# ARC_Lighting_v1_0.net
KiCad netlist of a schematic drawn in EAGLE
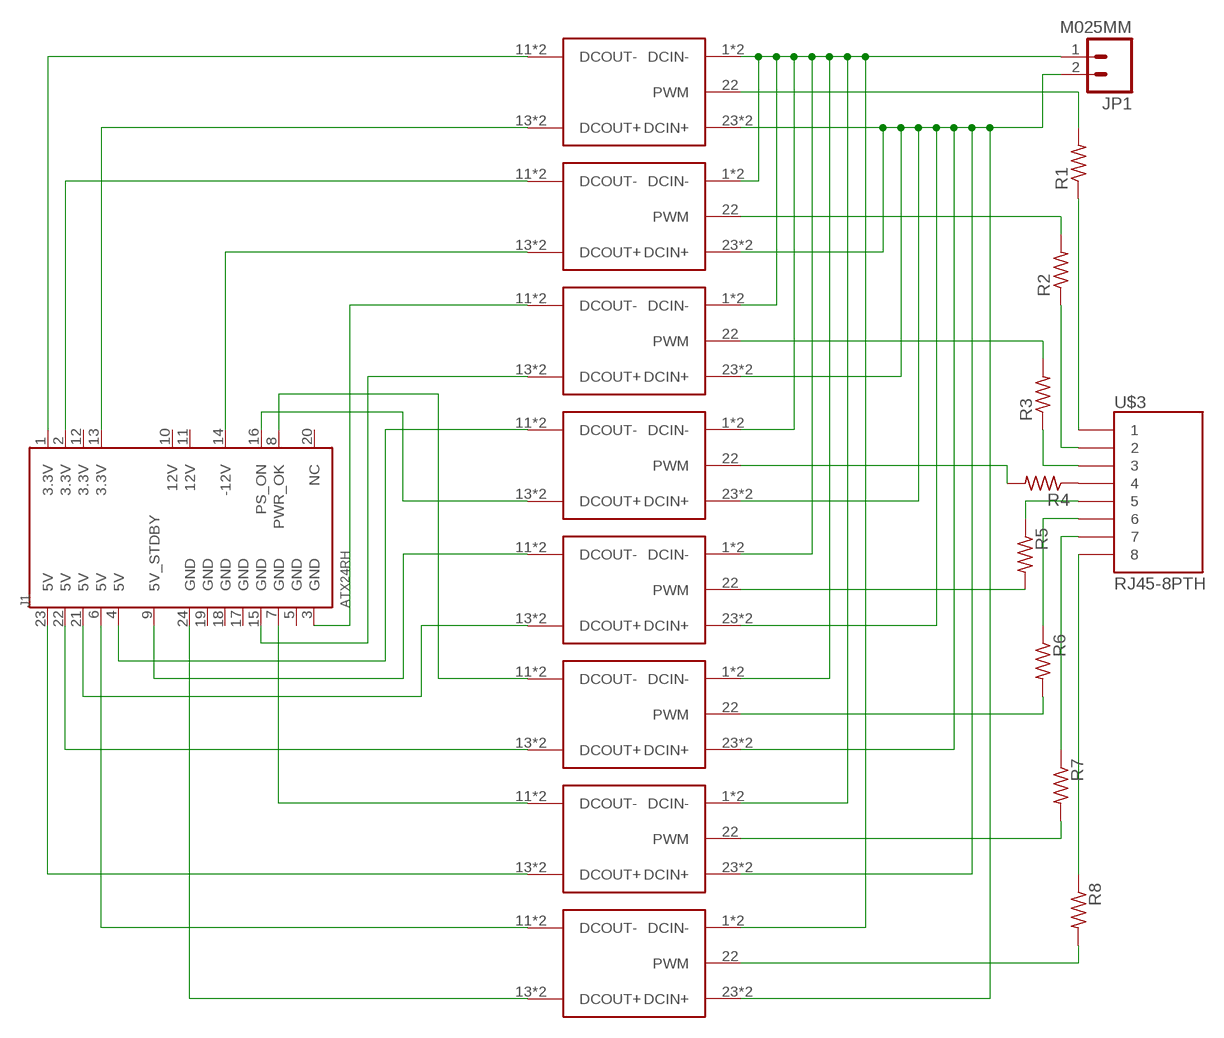
[diagram p0: schematic, sheet 1]

(export (version "E")
  (design (tool "Eeschema 10.0.6"))
  (components
    (comp (ref "J1")
      (value "ATX24RH")
      (footprint "eagle-import:ATX24_RIGHT_ANGLE")
      (libsource (lib "eagle-import") (part "ATX24RH"))
    )
    (comp (ref "JP1")
      (value "M025MM")
      (footprint "eagle-import:SCREWTERMINAL-5MM-2")
      (libsource (lib "eagle-import") (part "M025MM"))
    )
    (comp (ref "R1")
      (value "R-US_0204/7")
      (footprint "eagle-import:0204_7")
      (libsource (lib "eagle-import") (part "R-US_0204/7"))
    )
    (comp (ref "R2")
      (value "R-US_0204/7")
      (footprint "eagle-import:0204_7")
      (libsource (lib "eagle-import") (part "R-US_0204/7"))
    )
    (comp (ref "R3")
      (value "R-US_0204/7")
      (footprint "eagle-import:0204_7")
      (libsource (lib "eagle-import") (part "R-US_0204/7"))
    )
    (comp (ref "R4")
      (value "R-US_0204/7")
      (footprint "eagle-import:0204_7")
      (libsource (lib "eagle-import") (part "R-US_0204/7"))
    )
    (comp (ref "R5")
      (value "R-US_0204/7")
      (footprint "eagle-import:0204_7")
      (libsource (lib "eagle-import") (part "R-US_0204/7"))
    )
    (comp (ref "R6")
      (value "R-US_0204/7")
      (footprint "eagle-import:0204_7")
      (libsource (lib "eagle-import") (part "R-US_0204/7"))
    )
    (comp (ref "R7")
      (value "R-US_0204/7")
      (footprint "eagle-import:0204_7")
      (libsource (lib "eagle-import") (part "R-US_0204/7"))
    )
    (comp (ref "R8")
      (value "R-US_0204/7")
      (footprint "eagle-import:0204_7")
      (libsource (lib "eagle-import") (part "R-US_0204/7"))
    )
    (comp (ref "U$1")
      (value "1")
      (footprint "eagle-import:LDD_H")
      (libsource (lib "eagle-import") (part "LDD_H"))
    )
    (comp (ref "U$2")
      (value "2")
      (footprint "eagle-import:LDD_H")
      (libsource (lib "eagle-import") (part "LDD_H"))
    )
    (comp (ref "U$3")
      (value "RJ45-8PTH")
      (footprint "eagle-import:RJ45-8")
      (libsource (lib "eagle-import") (part "RJ45-8PTH"))
    )
    (comp (ref "U$4")
      (value "3")
      (footprint "eagle-import:LDD_H")
      (libsource (lib "eagle-import") (part "LDD_H"))
    )
    (comp (ref "U$5")
      (value "4")
      (footprint "eagle-import:LDD_H")
      (libsource (lib "eagle-import") (part "LDD_H"))
    )
    (comp (ref "U$6")
      (value "5")
      (footprint "eagle-import:LDD_H")
      (libsource (lib "eagle-import") (part "LDD_H"))
    )
    (comp (ref "U$7")
      (value "6")
      (footprint "eagle-import:LDD_H")
      (libsource (lib "eagle-import") (part "LDD_H"))
    )
    (comp (ref "U$8")
      (value "7")
      (footprint "eagle-import:LDD_H")
      (libsource (lib "eagle-import") (part "LDD_H"))
    )
    (comp (ref "U$9")
      (value "8")
      (footprint "eagle-import:LDD_H")
      (libsource (lib "eagle-import") (part "LDD_H"))
    )
  )
  (nets
    (net (code "1") (name "Net-(J1--12V)") (class "Default")
      (node (ref "J1") (pin "14") (pinfunction "-12V_14") (pintype "bidirectional"))
      (node (ref "U$2") (pin "13") (pinfunction "DCOUT+_13") (pintype "output"))
      (node (ref "U$2") (pin "14") (pinfunction "DCOUT+_14") (pintype "output"))
    )
    (net (code "2") (name "Net-(J1-3.3V-Pad1)") (class "Default")
      (node (ref "J1") (pin "1") (pinfunction "3.3V_1") (pintype "bidirectional"))
      (node (ref "U$1") (pin "11") (pinfunction "DCOUT-_11") (pintype "output"))
      (node (ref "U$1") (pin "12") (pinfunction "DCOUT-_12") (pintype "output"))
    )
    (net (code "3") (name "Net-(J1-3.3V-Pad2)") (class "Default")
      (node (ref "J1") (pin "2") (pinfunction "3.3V_2") (pintype "bidirectional"))
      (node (ref "U$2") (pin "11") (pinfunction "DCOUT-_11") (pintype "output"))
      (node (ref "U$2") (pin "12") (pinfunction "DCOUT-_12") (pintype "output"))
    )
    (net (code "4") (name "Net-(J1-3.3V-Pad13)") (class "Default")
      (node (ref "J1") (pin "13") (pinfunction "3.3V_13") (pintype "bidirectional"))
      (node (ref "U$1") (pin "13") (pinfunction "DCOUT+_13") (pintype "output"))
      (node (ref "U$1") (pin "14") (pinfunction "DCOUT+_14") (pintype "output"))
    )
    (net (code "5") (name "Net-(J1-5V-Pad4)") (class "Default")
      (node (ref "J1") (pin "4") (pinfunction "5V_4") (pintype "bidirectional"))
      (node (ref "U$5") (pin "11") (pinfunction "DCOUT-_11") (pintype "output"))
      (node (ref "U$5") (pin "12") (pinfunction "DCOUT-_12") (pintype "output"))
    )
    (net (code "6") (name "Net-(J1-5V-Pad6)") (class "Default")
      (node (ref "J1") (pin "6") (pinfunction "5V_6") (pintype "bidirectional"))
      (node (ref "U$9") (pin "11") (pinfunction "DCOUT-_11") (pintype "output"))
      (node (ref "U$9") (pin "12") (pinfunction "DCOUT-_12") (pintype "output"))
    )
    (net (code "7") (name "Net-(J1-5V-Pad21)") (class "Default")
      (node (ref "J1") (pin "21") (pinfunction "5V_21") (pintype "bidirectional"))
      (node (ref "U$6") (pin "13") (pinfunction "DCOUT+_13") (pintype "output"))
      (node (ref "U$6") (pin "14") (pinfunction "DCOUT+_14") (pintype "output"))
    )
    (net (code "8") (name "Net-(J1-5V-Pad22)") (class "Default")
      (node (ref "J1") (pin "22") (pinfunction "5V_22") (pintype "bidirectional"))
      (node (ref "U$7") (pin "13") (pinfunction "DCOUT+_13") (pintype "output"))
      (node (ref "U$7") (pin "14") (pinfunction "DCOUT+_14") (pintype "output"))
    )
    (net (code "9") (name "Net-(J1-5V-Pad23)") (class "Default")
      (node (ref "J1") (pin "23") (pinfunction "5V_23") (pintype "bidirectional"))
      (node (ref "U$8") (pin "13") (pinfunction "DCOUT+_13") (pintype "output"))
      (node (ref "U$8") (pin "14") (pinfunction "DCOUT+_14") (pintype "output"))
    )
    (net (code "10") (name "Net-(J1-5V_STDBY)") (class "Default")
      (node (ref "J1") (pin "9") (pinfunction "5V_STDBY_9") (pintype "bidirectional"))
      (node (ref "U$6") (pin "11") (pinfunction "DCOUT-_11") (pintype "output"))
      (node (ref "U$6") (pin "12") (pinfunction "DCOUT-_12") (pintype "output"))
    )
    (net (code "11") (name "Net-(J1-GND-Pad3)") (class "Default")
      (node (ref "J1") (pin "3") (pinfunction "GND_3") (pintype "bidirectional"))
      (node (ref "U$4") (pin "11") (pinfunction "DCOUT-_11") (pintype "output"))
      (node (ref "U$4") (pin "12") (pinfunction "DCOUT-_12") (pintype "output"))
    )
    (net (code "12") (name "Net-(J1-GND-Pad7)") (class "Default")
      (node (ref "J1") (pin "7") (pinfunction "GND_7") (pintype "bidirectional"))
      (node (ref "U$8") (pin "11") (pinfunction "DCOUT-_11") (pintype "output"))
      (node (ref "U$8") (pin "12") (pinfunction "DCOUT-_12") (pintype "output"))
    )
    (net (code "13") (name "Net-(J1-GND-Pad15)") (class "Default")
      (node (ref "J1") (pin "15") (pinfunction "GND_15") (pintype "bidirectional"))
      (node (ref "U$4") (pin "13") (pinfunction "DCOUT+_13") (pintype "output"))
      (node (ref "U$4") (pin "14") (pinfunction "DCOUT+_14") (pintype "output"))
    )
    (net (code "14") (name "Net-(J1-GND-Pad24)") (class "Default")
      (node (ref "J1") (pin "24") (pinfunction "GND_24") (pintype "bidirectional"))
      (node (ref "U$9") (pin "13") (pinfunction "DCOUT+_13") (pintype "output"))
      (node (ref "U$9") (pin "14") (pinfunction "DCOUT+_14") (pintype "output"))
    )
    (net (code "15") (name "Net-(J1-PS_ON)") (class "Default")
      (node (ref "J1") (pin "16") (pinfunction "PS_ON_16") (pintype "bidirectional"))
      (node (ref "U$5") (pin "13") (pinfunction "DCOUT+_13") (pintype "output"))
      (node (ref "U$5") (pin "14") (pinfunction "DCOUT+_14") (pintype "output"))
    )
    (net (code "16") (name "Net-(J1-PWR_OK)") (class "Default")
      (node (ref "J1") (pin "8") (pinfunction "PWR_OK_8") (pintype "bidirectional"))
      (node (ref "U$7") (pin "11") (pinfunction "DCOUT-_11") (pintype "output"))
      (node (ref "U$7") (pin "12") (pinfunction "DCOUT-_12") (pintype "output"))
    )
    (net (code "17") (name "Net-(JP1-Pad1)") (class "Default")
      (node (ref "JP1") (pin "1") (pinfunction "1_1") (pintype "passive"))
      (node (ref "U$1") (pin "1") (pinfunction "DCIN-_1") (pintype "input"))
      (node (ref "U$1") (pin "2") (pinfunction "DCIN-_2") (pintype "input"))
      (node (ref "U$2") (pin "1") (pinfunction "DCIN-_1") (pintype "input"))
      (node (ref "U$2") (pin "2") (pinfunction "DCIN-_2") (pintype "input"))
      (node (ref "U$4") (pin "1") (pinfunction "DCIN-_1") (pintype "input"))
      (node (ref "U$4") (pin "2") (pinfunction "DCIN-_2") (pintype "input"))
      (node (ref "U$5") (pin "1") (pinfunction "DCIN-_1") (pintype "input"))
      (node (ref "U$5") (pin "2") (pinfunction "DCIN-_2") (pintype "input"))
      (node (ref "U$6") (pin "1") (pinfunction "DCIN-_1") (pintype "input"))
      (node (ref "U$6") (pin "2") (pinfunction "DCIN-_2") (pintype "input"))
      (node (ref "U$7") (pin "1") (pinfunction "DCIN-_1") (pintype "input"))
      (node (ref "U$7") (pin "2") (pinfunction "DCIN-_2") (pintype "input"))
      (node (ref "U$8") (pin "1") (pinfunction "DCIN-_1") (pintype "input"))
      (node (ref "U$8") (pin "2") (pinfunction "DCIN-_2") (pintype "input"))
      (node (ref "U$9") (pin "1") (pinfunction "DCIN-_1") (pintype "input"))
      (node (ref "U$9") (pin "2") (pinfunction "DCIN-_2") (pintype "input"))
    )
    (net (code "18") (name "Net-(JP1-Pad2)") (class "Default")
      (node (ref "JP1") (pin "2") (pinfunction "2_2") (pintype "passive"))
      (node (ref "U$1") (pin "23") (pinfunction "DCIN+_23") (pintype "input"))
      (node (ref "U$1") (pin "24") (pinfunction "DCIN+_24") (pintype "input"))
      (node (ref "U$2") (pin "23") (pinfunction "DCIN+_23") (pintype "input"))
      (node (ref "U$2") (pin "24") (pinfunction "DCIN+_24") (pintype "input"))
      (node (ref "U$4") (pin "23") (pinfunction "DCIN+_23") (pintype "input"))
      (node (ref "U$4") (pin "24") (pinfunction "DCIN+_24") (pintype "input"))
      (node (ref "U$5") (pin "23") (pinfunction "DCIN+_23") (pintype "input"))
      (node (ref "U$5") (pin "24") (pinfunction "DCIN+_24") (pintype "input"))
      (node (ref "U$6") (pin "23") (pinfunction "DCIN+_23") (pintype "input"))
      (node (ref "U$6") (pin "24") (pinfunction "DCIN+_24") (pintype "input"))
      (node (ref "U$7") (pin "23") (pinfunction "DCIN+_23") (pintype "input"))
      (node (ref "U$7") (pin "24") (pinfunction "DCIN+_24") (pintype "input"))
      (node (ref "U$8") (pin "23") (pinfunction "DCIN+_23") (pintype "input"))
      (node (ref "U$8") (pin "24") (pinfunction "DCIN+_24") (pintype "input"))
      (node (ref "U$9") (pin "23") (pinfunction "DCIN+_23") (pintype "input"))
      (node (ref "U$9") (pin "24") (pinfunction "DCIN+_24") (pintype "input"))
    )
    (net (code "19") (name "Net-(R1-Pad1)") (class "Default")
      (node (ref "R1") (pin "1") (pinfunction "1_1") (pintype "passive"))
      (node (ref "U$3") (pin "1") (pinfunction "1_1") (pintype "bidirectional"))
    )
    (net (code "20") (name "Net-(R2-Pad1)") (class "Default")
      (node (ref "R2") (pin "1") (pinfunction "1_1") (pintype "passive"))
      (node (ref "U$3") (pin "2") (pinfunction "2_2") (pintype "bidirectional"))
    )
    (net (code "21") (name "Net-(R3-Pad1)") (class "Default")
      (node (ref "R3") (pin "1") (pinfunction "1_1") (pintype "passive"))
      (node (ref "U$3") (pin "3") (pinfunction "3_3") (pintype "bidirectional"))
    )
    (net (code "22") (name "Net-(R4-Pad1)") (class "Default")
      (node (ref "R4") (pin "1") (pinfunction "1_1") (pintype "passive"))
      (node (ref "U$3") (pin "4") (pinfunction "4_4") (pintype "bidirectional"))
    )
    (net (code "23") (name "Net-(R5-Pad1)") (class "Default")
      (node (ref "R5") (pin "1") (pinfunction "1_1") (pintype "passive"))
      (node (ref "U$3") (pin "5") (pinfunction "5_5") (pintype "bidirectional"))
    )
    (net (code "24") (name "Net-(R6-Pad1)") (class "Default")
      (node (ref "R6") (pin "1") (pinfunction "1_1") (pintype "passive"))
      (node (ref "U$3") (pin "6") (pinfunction "6_6") (pintype "bidirectional"))
    )
    (net (code "25") (name "Net-(R7-Pad1)") (class "Default")
      (node (ref "R7") (pin "1") (pinfunction "1_1") (pintype "passive"))
      (node (ref "U$3") (pin "7") (pinfunction "7_7") (pintype "bidirectional"))
    )
    (net (code "26") (name "Net-(R8-Pad1)") (class "Default")
      (node (ref "R8") (pin "1") (pinfunction "1_1") (pintype "passive"))
      (node (ref "U$3") (pin "8") (pinfunction "8_8") (pintype "bidirectional"))
    )
    (net (code "27") (name "Net-(U$1-PWM)") (class "Default")
      (node (ref "R1") (pin "2") (pinfunction "2_2") (pintype "passive"))
      (node (ref "U$1") (pin "22") (pinfunction "PWM_22") (pintype "bidirectional"))
    )
    (net (code "28") (name "Net-(U$2-PWM)") (class "Default")
      (node (ref "R2") (pin "2") (pinfunction "2_2") (pintype "passive"))
      (node (ref "U$2") (pin "22") (pinfunction "PWM_22") (pintype "bidirectional"))
    )
    (net (code "29") (name "Net-(U$4-PWM)") (class "Default")
      (node (ref "R3") (pin "2") (pinfunction "2_2") (pintype "passive"))
      (node (ref "U$4") (pin "22") (pinfunction "PWM_22") (pintype "bidirectional"))
    )
    (net (code "30") (name "Net-(U$5-PWM)") (class "Default")
      (node (ref "R4") (pin "2") (pinfunction "2_2") (pintype "passive"))
      (node (ref "U$5") (pin "22") (pinfunction "PWM_22") (pintype "bidirectional"))
    )
    (net (code "31") (name "Net-(U$6-PWM)") (class "Default")
      (node (ref "R5") (pin "2") (pinfunction "2_2") (pintype "passive"))
      (node (ref "U$6") (pin "22") (pinfunction "PWM_22") (pintype "bidirectional"))
    )
    (net (code "32") (name "Net-(U$7-PWM)") (class "Default")
      (node (ref "R6") (pin "2") (pinfunction "2_2") (pintype "passive"))
      (node (ref "U$7") (pin "22") (pinfunction "PWM_22") (pintype "bidirectional"))
    )
    (net (code "33") (name "Net-(U$8-PWM)") (class "Default")
      (node (ref "R7") (pin "2") (pinfunction "2_2") (pintype "passive"))
      (node (ref "U$8") (pin "22") (pinfunction "PWM_22") (pintype "bidirectional"))
    )
    (net (code "34") (name "Net-(U$9-PWM)") (class "Default")
      (node (ref "R8") (pin "2") (pinfunction "2_2") (pintype "passive"))
      (node (ref "U$9") (pin "22") (pinfunction "PWM_22") (pintype "bidirectional"))
    )
    (net (code "35") (name "unconnected-(J1-3.3V-Pad12)") (class "Default")
      (node (ref "J1") (pin "12") (pinfunction "3.3V_12") (pintype "bidirectional"))
    )
    (net (code "36") (name "unconnected-(J1-12V-Pad10)") (class "Default")
      (node (ref "J1") (pin "10") (pinfunction "12V_10") (pintype "bidirectional"))
    )
    (net (code "37") (name "unconnected-(J1-12V-Pad11)") (class "Default")
      (node (ref "J1") (pin "11") (pinfunction "12V_11") (pintype "bidirectional"))
    )
    (net (code "38") (name "unconnected-(J1-GND-Pad5)") (class "Default")
      (node (ref "J1") (pin "5") (pinfunction "GND_5") (pintype "bidirectional"))
    )
    (net (code "39") (name "unconnected-(J1-GND-Pad17)") (class "Default")
      (node (ref "J1") (pin "17") (pinfunction "GND_17") (pintype "bidirectional"))
    )
    (net (code "40") (name "unconnected-(J1-GND-Pad18)") (class "Default")
      (node (ref "J1") (pin "18") (pinfunction "GND_18") (pintype "bidirectional"))
    )
    (net (code "41") (name "unconnected-(J1-GND-Pad19)") (class "Default")
      (node (ref "J1") (pin "19") (pinfunction "GND_19") (pintype "bidirectional"))
    )
    (net (code "42") (name "unconnected-(J1-NC-Pad20)") (class "Default")
      (node (ref "J1") (pin "20") (pinfunction "NC_20") (pintype "bidirectional"))
    )
  )
)
